# 04_-_LEVEL_SHIFTER.net
KiCad netlist of a schematic drawn in Altium Designer
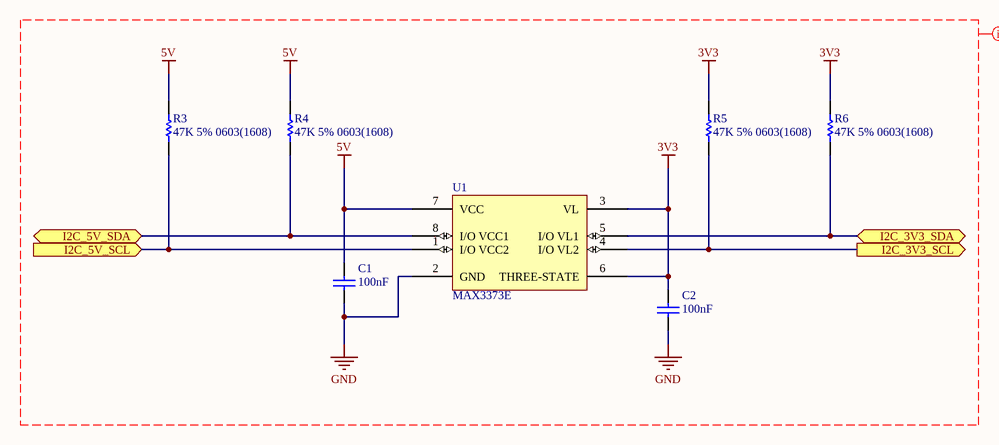
[diagram p0: [04] - LEVEL_SHIFTER.SchDoc]

(export (version "E")
  (design (tool "Eeschema 10.0.6"))
  (components
    (comp (ref "C1")
      (value "100nF")
      (footprint "CAPC0603(1608)100_L")
      (description "CAP 100nF 50V ±10% 0603 (1608 Metric) Thickness 1mm SMD")
      (fields
        (field (name "TOLERANCE") "±10%")
        (field (name "MANUFACTURER PART NUMBER") "C0603C104K5RACAUTO")
      )
      (libsource (lib "Altium Content Vault") (part "CMP-1035-02592-1"))
    )
    (comp (ref "C2")
      (value "100nF")
      (footprint "CAPC0603(1608)100_L")
      (description "CAP 100nF 50V ±10% 0603 (1608 Metric) Thickness 1mm SMD")
      (fields
        (field (name "TOLERANCE") "±10%")
        (field (name "MANUFACTURER PART NUMBER") "C0603C104K5RACAUTO")
      )
      (libsource (lib "Altium Content Vault") (part "CMP-1035-02592-1"))
    )
    (comp (ref "R3")
      (value "47K 5% 0603(1608)")
      (footprint "RESC0603(1608)_L")
      (description "47K 0.1W 5% 0603 (1608 Metric)  SMD")
      (fields (field (name "TOLERANCE") "5 %") (field (name "POWER") "0.1 W"))
      (libsource (lib "Altium Content Vault") (part "CMP-1012-00114-1"))
    )
    (comp (ref "R4")
      (value "47K 5% 0603(1608)")
      (footprint "RESC0603(1608)_L")
      (description "47K 0.1W 5% 0603 (1608 Metric)  SMD")
      (fields (field (name "TOLERANCE") "5 %") (field (name "POWER") "0.1 W"))
      (libsource (lib "Altium Content Vault") (part "CMP-1012-00114-1"))
    )
    (comp (ref "R5")
      (value "47K 5% 0603(1608)")
      (footprint "RESC0603(1608)_L")
      (description "47K 0.1W 5% 0603 (1608 Metric)  SMD")
      (fields (field (name "TOLERANCE") "5 %") (field (name "POWER") "0.1 W"))
      (libsource (lib "Altium Content Vault") (part "CMP-1012-00114-1"))
    )
    (comp (ref "R6")
      (value "47K 5% 0603(1608)")
      (footprint "RESC0603(1608)_L")
      (description "47K 0.1W 5% 0603 (1608 Metric)  SMD")
      (fields (field (name "TOLERANCE") "5 %") (field (name "POWER") "0.1 W"))
      (libsource (lib "Altium Content Vault") (part "CMP-1012-00114-1"))
    )
    (comp (ref "U1") (value "MAX3373E") (footprint "MAX3373E") (libsource (lib "MAX3373E") (part "MAX3373E")))
  )
  (nets
    (net (code "1") (name "/I2C_3V3_SCL") (class "Default")
      (node (ref "R5") (pin "2") (pinfunction "2_2") (pintype "passive"))
      (node (ref "U1") (pin "4") (pinfunction "I/O_VL2_4") (pintype "bidirectional"))
    )
    (net (code "2") (name "/I2C_3V3_SDA") (class "Default")
      (node (ref "R6") (pin "2") (pinfunction "2_2") (pintype "passive"))
      (node (ref "U1") (pin "5") (pinfunction "I/O_VL1_5") (pintype "bidirectional"))
    )
    (net (code "3") (name "/I2C_5V_SCL") (class "Default")
      (node (ref "R3") (pin "2") (pinfunction "2_2") (pintype "passive"))
      (node (ref "U1") (pin "1") (pinfunction "I/O_VCC2_1") (pintype "bidirectional"))
    )
    (net (code "4") (name "/I2C_5V_SDA") (class "Default")
      (node (ref "R4") (pin "2") (pinfunction "2_2") (pintype "passive"))
      (node (ref "U1") (pin "8") (pinfunction "I/O_VCC1_8") (pintype "bidirectional"))
    )
    (net (code "5") (name "3V3") (class "Default")
      (node (ref "C2") (pin "2") (pinfunction "2_2") (pintype "passive"))
      (node (ref "R5") (pin "1") (pinfunction "1_1") (pintype "passive"))
      (node (ref "R6") (pin "1") (pinfunction "1_1") (pintype "passive"))
      (node (ref "U1") (pin "3") (pinfunction "VL_3") (pintype "power_in"))
      (node (ref "U1") (pin "6") (pinfunction "THREE-STATE_6") (pintype "power_in"))
    )
    (net (code "6") (name "5V") (class "Default")
      (node (ref "C1") (pin "2") (pinfunction "2_2") (pintype "passive"))
      (node (ref "R3") (pin "1") (pinfunction "1_1") (pintype "passive"))
      (node (ref "R4") (pin "1") (pinfunction "1_1") (pintype "passive"))
      (node (ref "U1") (pin "7") (pinfunction "VCC_7") (pintype "power_in"))
    )
    (net (code "7") (name "GND") (class "Default")
      (node (ref "C1") (pin "1") (pinfunction "1_1") (pintype "passive"))
      (node (ref "C2") (pin "1") (pinfunction "1_1") (pintype "passive"))
      (node (ref "U1") (pin "2") (pinfunction "GND_2") (pintype "power_in"))
    )
  )
)
